# New_Multirotor_GPS.net
KiCad netlist of a schematic drawn in EAGLE
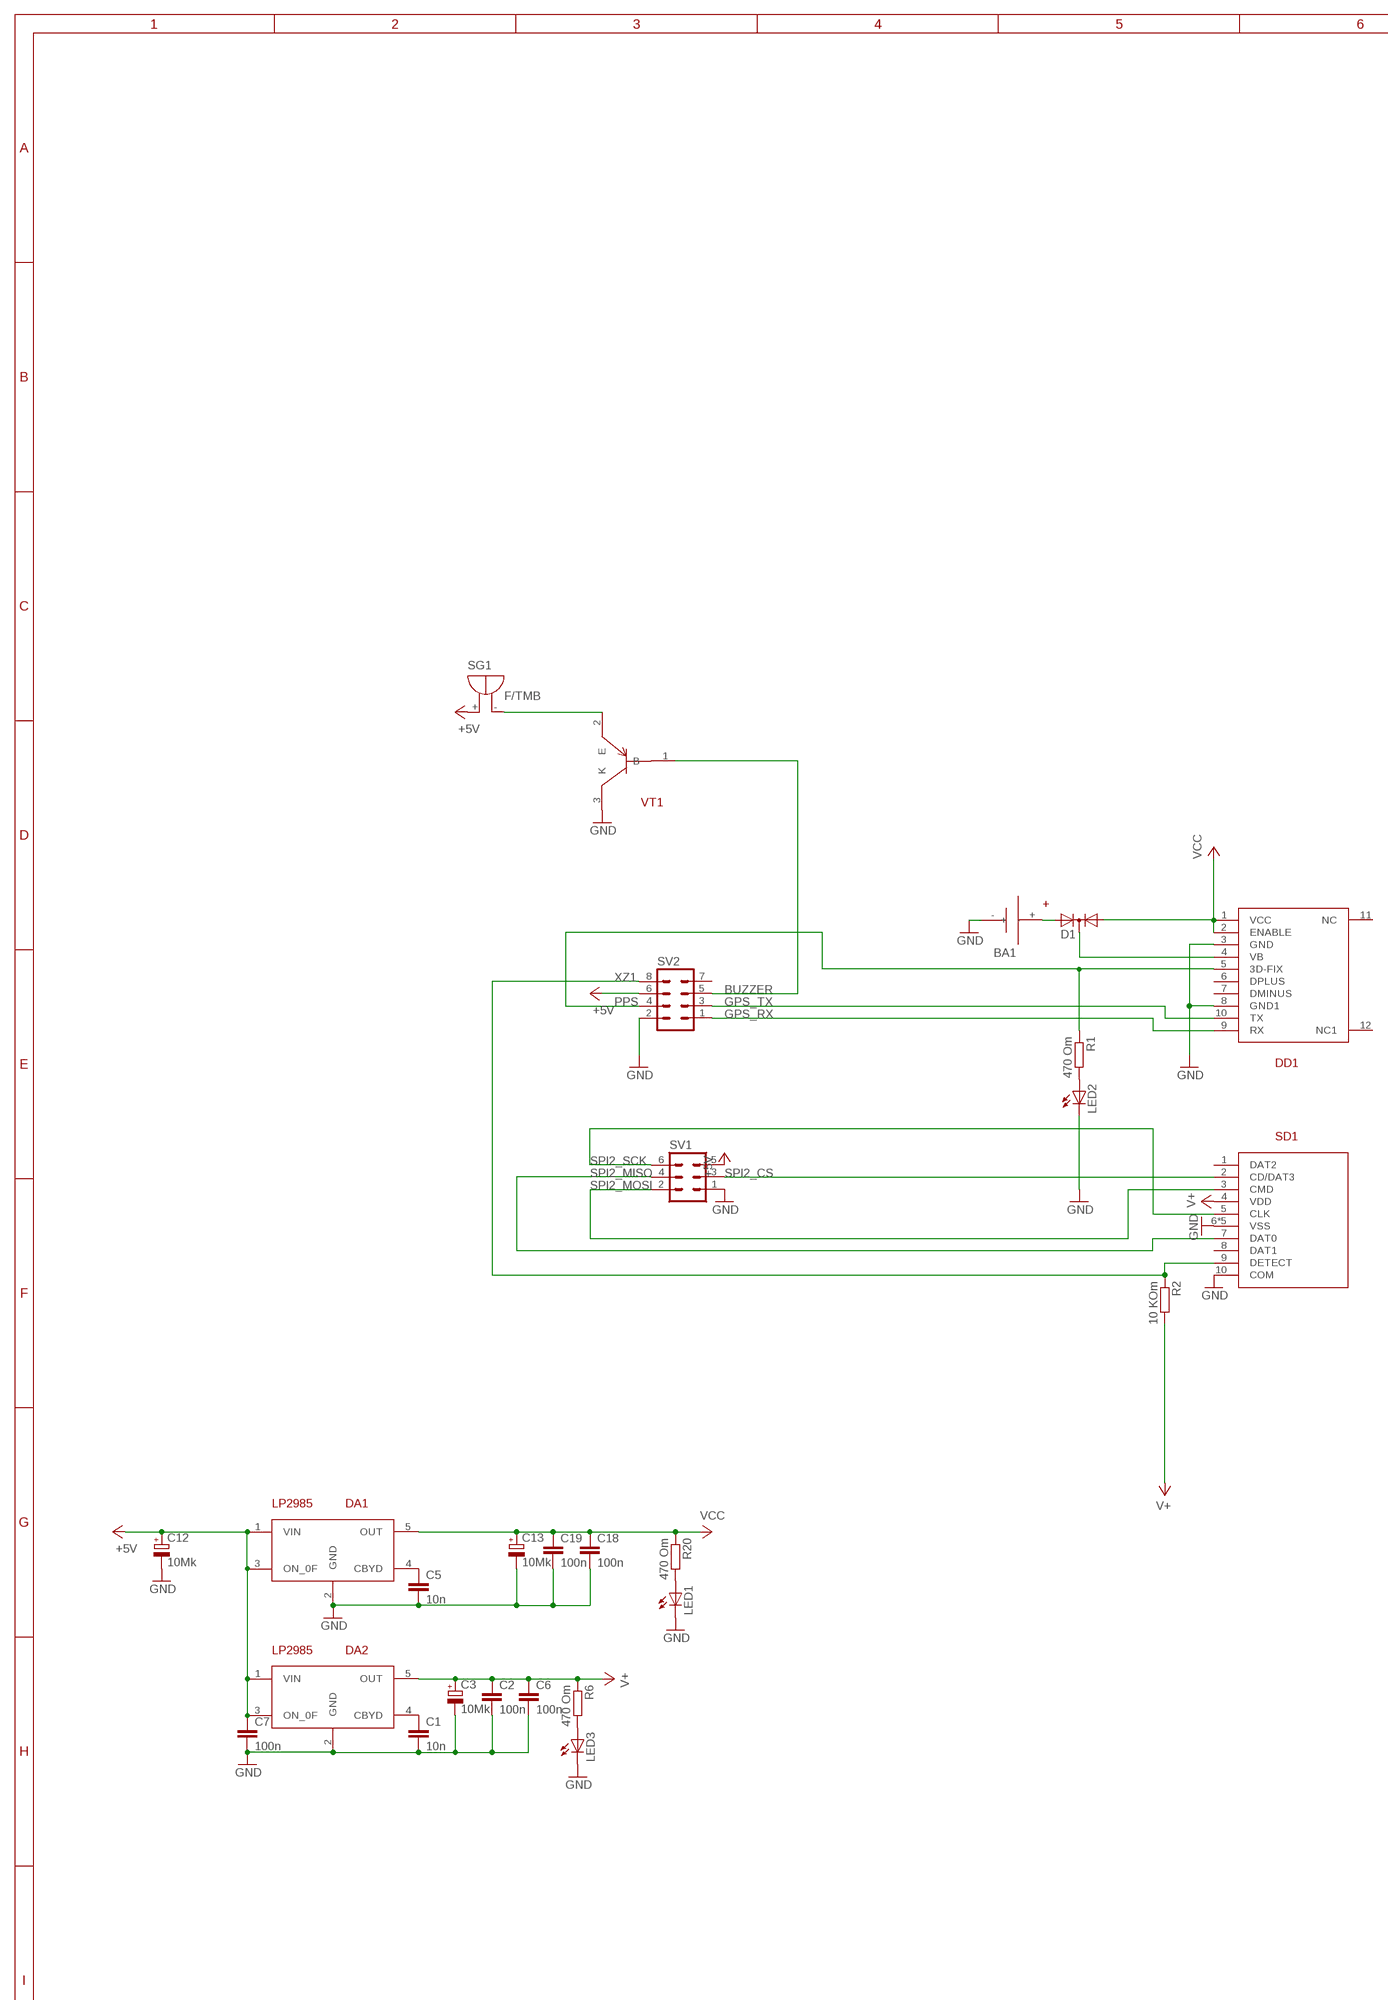
[diagram p0: schematic, sheet 1, part 1 of 2]
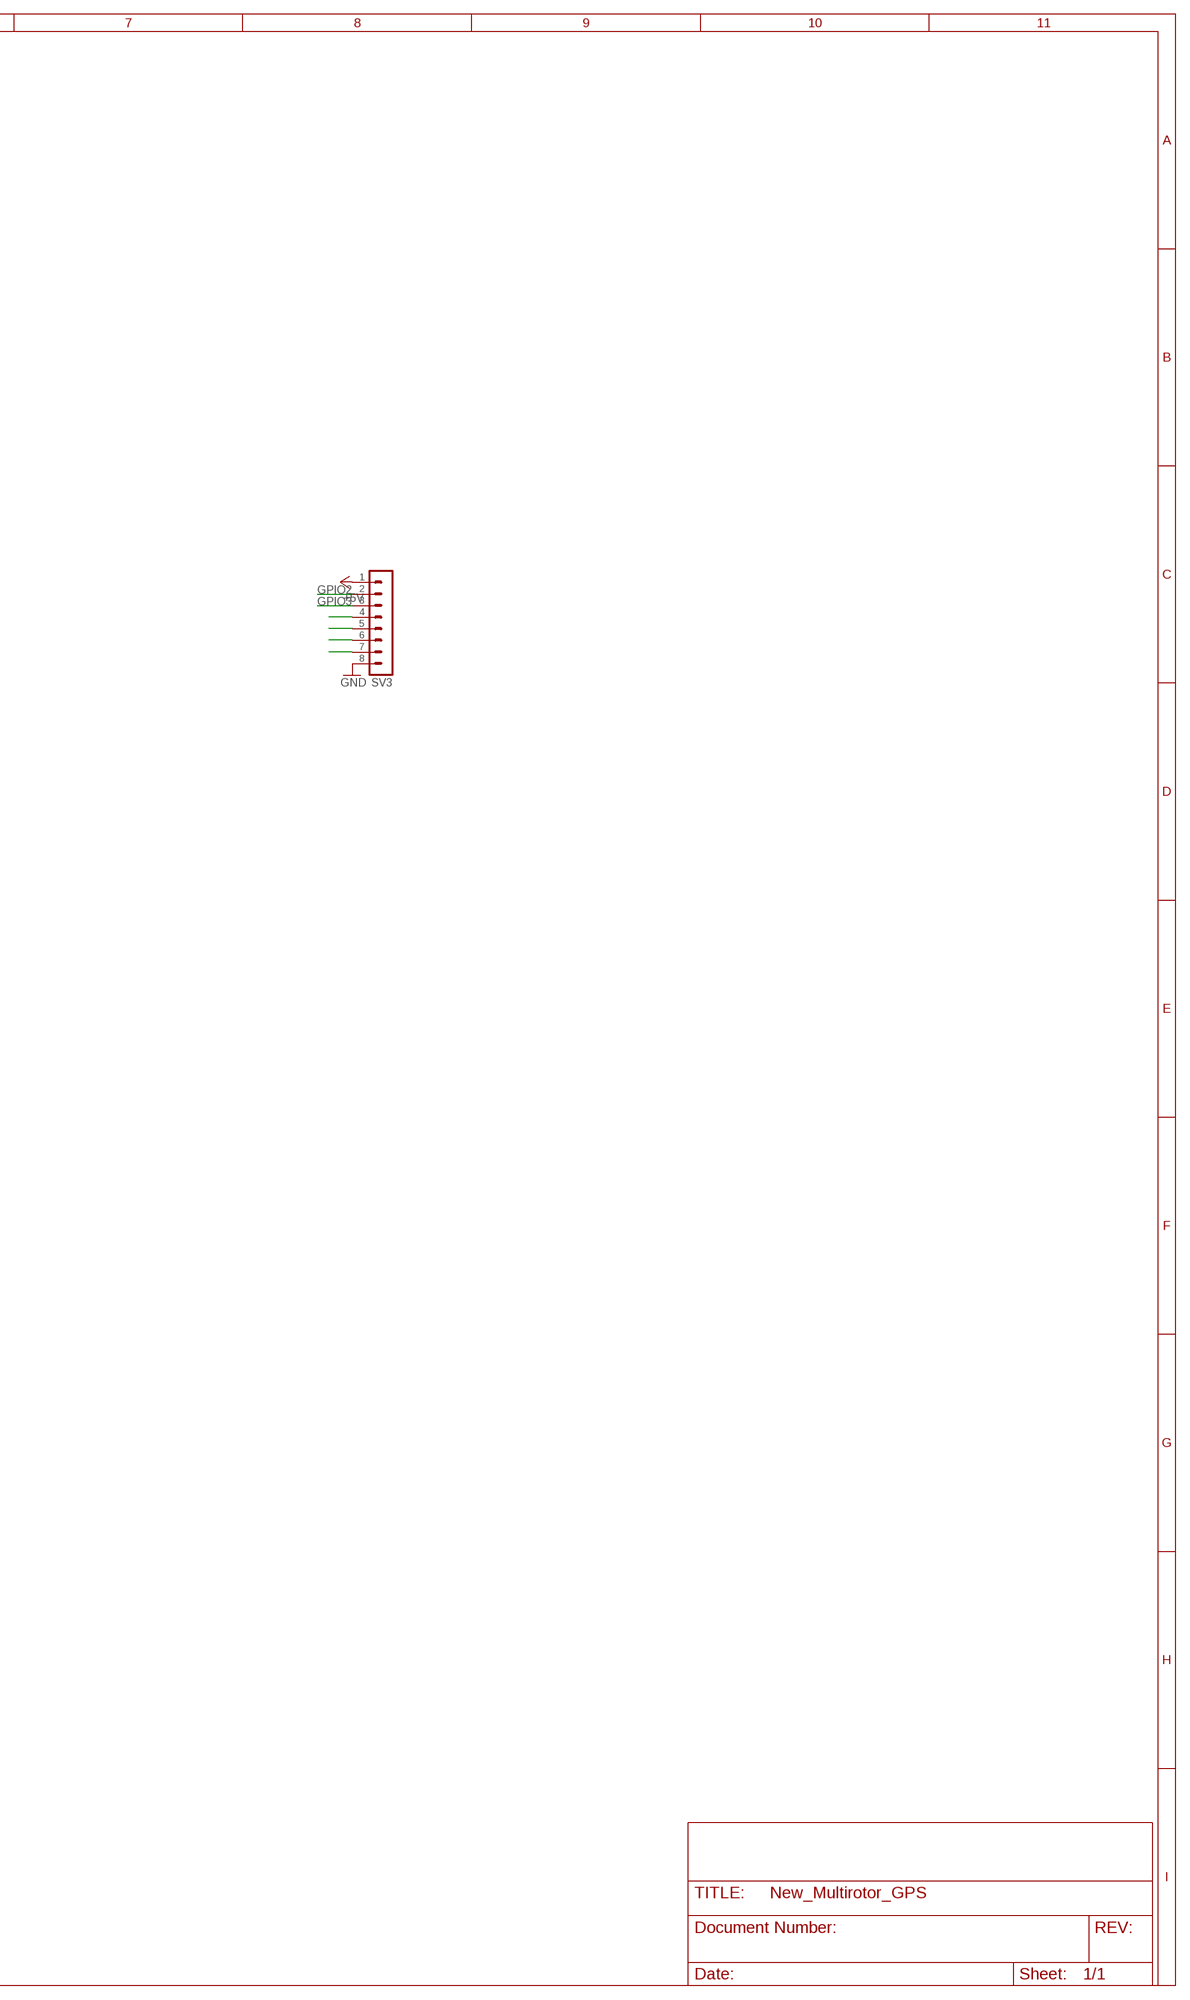
[diagram p1: schematic, sheet 1, part 2 of 2]

(export (version "E")
  (design (tool "Eeschema 10.0.6"))
  (components
    (comp (ref "BA1")
      (value "BAT")
      (footprint "eagle-import:BAT")
      (libsource (lib "eagle-import") (part "BAT"))
    )
    (comp (ref "C1")
      (value "10n")
      (footprint "eagle-import:C0603K")
      (libsource (lib "eagle-import") (part "C-EUC0603K"))
    )
    (comp (ref "C2")
      (value "100n")
      (footprint "eagle-import:C0603K")
      (libsource (lib "eagle-import") (part "C-EUC0603K"))
    )
    (comp (ref "C3")
      (value "10Mk")
      (footprint "eagle-import:A_3216-18W")
      (libsource (lib "eagle-import") (part "CPOL-EUA/3216-18W"))
    )
    (comp (ref "C5")
      (value "10n")
      (footprint "eagle-import:C0603K")
      (libsource (lib "eagle-import") (part "C-EUC0603K"))
    )
    (comp (ref "C6")
      (value "100n")
      (footprint "eagle-import:C0603K")
      (libsource (lib "eagle-import") (part "C-EUC0603K"))
    )
    (comp (ref "C7")
      (value "100n")
      (footprint "eagle-import:C0603K")
      (libsource (lib "eagle-import") (part "C-EUC0603K"))
    )
    (comp (ref "C12")
      (value "10Mk")
      (footprint "eagle-import:A_3216-18W")
      (libsource (lib "eagle-import") (part "CPOL-EUA/3216-18W"))
    )
    (comp (ref "C13")
      (value "10Mk")
      (footprint "eagle-import:A_3216-18W")
      (libsource (lib "eagle-import") (part "CPOL-EUA/3216-18W"))
    )
    (comp (ref "C18")
      (value "100n")
      (footprint "eagle-import:C0603K")
      (libsource (lib "eagle-import") (part "C-EUC0603K"))
    )
    (comp (ref "C19")
      (value "100n")
      (footprint "eagle-import:C0603K")
      (libsource (lib "eagle-import") (part "C-EUC0603K"))
    )
    (comp (ref "D1")
      (value "DIODE-2AC|CASOT23")
      (footprint "eagle-import:SOT23")
      (libsource (lib "eagle-import") (part "DIODE-2AC|CASOT23"))
    )
    (comp (ref "DA1")
      (value "LP2985")
      (footprint "eagle-import:SOT23-5L")
      (libsource (lib "eagle-import") (part "3.3"))
    )
    (comp (ref "DA2")
      (value "LP2985")
      (footprint "eagle-import:SOT23-5L")
      (libsource (lib "eagle-import") (part "3.3"))
    )
    (comp (ref "DD1")
      (value "FGPMMOPA6B")
      (footprint "eagle-import:FGPMMOPA6B")
      (libsource (lib "eagle-import") (part "FGPMMOPA6B"))
    )
    (comp (ref "LED1")
      (value "LEDCHIPLED_0603")
      (footprint "eagle-import:CHIPLED_0603")
      (libsource (lib "eagle-import") (part "LEDCHIPLED_0603"))
    )
    (comp (ref "LED2")
      (value "LEDCHIPLED_0603")
      (footprint "eagle-import:CHIPLED_0603")
      (libsource (lib "eagle-import") (part "LEDCHIPLED_0603"))
    )
    (comp (ref "LED3")
      (value "LEDCHIPLED_0603")
      (footprint "eagle-import:CHIPLED_0603")
      (libsource (lib "eagle-import") (part "LEDCHIPLED_0603"))
    )
    (comp (ref "R1")
      (value "470 Om")
      (footprint "eagle-import:R0603")
      (libsource (lib "eagle-import") (part "R-EU_R0603"))
    )
    (comp (ref "R2")
      (value "10 KOm")
      (footprint "eagle-import:R0603")
      (libsource (lib "eagle-import") (part "R-EU_R0603"))
    )
    (comp (ref "R6")
      (value "470 Om")
      (footprint "eagle-import:R0603")
      (libsource (lib "eagle-import") (part "R-EU_R0603"))
    )
    (comp (ref "R20")
      (value "470 Om")
      (footprint "eagle-import:R0603")
      (libsource (lib "eagle-import") (part "R-EU_R0603"))
    )
    (comp (ref "SD1")
      (value "MICROCD_MAIN")
      (footprint "eagle-import:MICROSD_MAIN")
      (libsource (lib "eagle-import") (part "MICROCD_MAIN"))
    )
    (comp (ref "SG1")
      (value "F/TMB")
      (footprint "eagle-import:F_TMB")
      (libsource (lib "eagle-import") (part "F/TMB"))
    )
    (comp (ref "SV1")
      (value "MA03-2")
      (footprint "eagle-import:MA03-2")
      (libsource (lib "eagle-import") (part "MA03-2"))
    )
    (comp (ref "SV2")
      (value "MA04-2")
      (footprint "eagle-import:MA04-2")
      (libsource (lib "eagle-import") (part "MA04-2"))
    )
    (comp (ref "SV3")
      (value "MA08-1")
      (footprint "eagle-import:MA08-1")
      (libsource (lib "eagle-import") (part "MA08-1"))
    )
    (comp (ref "VT1")
      (value "MMBT3906")
      (footprint "eagle-import:SOT23B-3")
      (libsource (lib "eagle-import") (part "MMBT3906"))
    )
  )
  (nets
    (net (code "1") (name "+5V") (class "Default")
      (node (ref "C12") (pin "+") (pinfunction "+_+") (pintype "passive"))
      (node (ref "C7") (pin "1") (pinfunction "1_1") (pintype "passive"))
      (node (ref "DA1") (pin "1") (pinfunction "VIN_1") (pintype "bidirectional"))
      (node (ref "DA1") (pin "3") (pinfunction "ON_0F_3") (pintype "bidirectional"))
      (node (ref "DA2") (pin "1") (pinfunction "VIN_1") (pintype "bidirectional"))
      (node (ref "DA2") (pin "3") (pinfunction "ON_0F_3") (pintype "bidirectional"))
      (node (ref "SG1") (pin "+") (pinfunction "+_+") (pintype "passive"))
      (node (ref "SV1") (pin "5") (pinfunction "5_5") (pintype "passive"))
      (node (ref "SV2") (pin "6") (pinfunction "6_6") (pintype "passive"))
      (node (ref "SV3") (pin "1") (pinfunction "1_1") (pintype "passive"))
    )
    (net (code "2") (name "/BUZZER") (class "Default")
      (node (ref "SV2") (pin "5") (pinfunction "5_5") (pintype "passive"))
      (node (ref "VT1") (pin "1") (pinfunction "B_1") (pintype "bidirectional"))
    )
    (net (code "3") (name "/GPIO2") (class "Default")
      (node (ref "SV3") (pin "2") (pinfunction "2_2") (pintype "passive"))
    )
    (net (code "4") (name "/GPIO3") (class "Default")
      (node (ref "SV3") (pin "3") (pinfunction "3_3") (pintype "passive"))
    )
    (net (code "5") (name "/GPS_RX") (class "Default")
      (node (ref "DD1") (pin "9") (pinfunction "RX_9") (pintype "bidirectional"))
      (node (ref "SV2") (pin "1") (pinfunction "1_1") (pintype "passive"))
    )
    (net (code "6") (name "/GPS_TX") (class "Default")
      (node (ref "DD1") (pin "10") (pinfunction "TX_10") (pintype "bidirectional"))
      (node (ref "SV2") (pin "3") (pinfunction "3_3") (pintype "passive"))
    )
    (net (code "7") (name "/PPS") (class "Default")
      (node (ref "DD1") (pin "5") (pinfunction "3D-FIX_5") (pintype "bidirectional"))
      (node (ref "R1") (pin "1") (pinfunction "1_1") (pintype "passive"))
      (node (ref "SV2") (pin "4") (pinfunction "4_4") (pintype "passive"))
    )
    (net (code "8") (name "/SPI2_CS") (class "Default")
      (node (ref "SD1") (pin "2") (pinfunction "CD/DAT3_2") (pintype "bidirectional"))
      (node (ref "SV1") (pin "3") (pinfunction "3_3") (pintype "passive"))
    )
    (net (code "9") (name "/SPI2_MISO") (class "Default")
      (node (ref "SD1") (pin "7") (pinfunction "DAT0_7") (pintype "bidirectional"))
      (node (ref "SV1") (pin "4") (pinfunction "4_4") (pintype "passive"))
    )
    (net (code "10") (name "/SPI2_MOSI") (class "Default")
      (node (ref "SD1") (pin "3") (pinfunction "CMD_3") (pintype "bidirectional"))
      (node (ref "SV1") (pin "2") (pinfunction "2_2") (pintype "passive"))
    )
    (net (code "11") (name "/SPI2_SCK") (class "Default")
      (node (ref "SD1") (pin "5") (pinfunction "CLK_5") (pintype "bidirectional"))
      (node (ref "SV1") (pin "6") (pinfunction "6_6") (pintype "passive"))
    )
    (net (code "12") (name "/XZ1") (class "Default")
      (node (ref "R2") (pin "1") (pinfunction "1_1") (pintype "passive"))
      (node (ref "SD1") (pin "9") (pinfunction "DETECT_9") (pintype "bidirectional"))
      (node (ref "SV2") (pin "8") (pinfunction "8_8") (pintype "passive"))
    )
    (net (code "13") (name "GND") (class "Default")
      (node (ref "BA1") (pin "-") (pinfunction "-_-") (pintype "power_in"))
      (node (ref "C1") (pin "2") (pinfunction "2_2") (pintype "passive"))
      (node (ref "C12") (pin "-") (pinfunction "-_-") (pintype "passive"))
      (node (ref "C13") (pin "-") (pinfunction "-_-") (pintype "passive"))
      (node (ref "C18") (pin "2") (pinfunction "2_2") (pintype "passive"))
      (node (ref "C19") (pin "2") (pinfunction "2_2") (pintype "passive"))
      (node (ref "C2") (pin "2") (pinfunction "2_2") (pintype "passive"))
      (node (ref "C3") (pin "-") (pinfunction "-_-") (pintype "passive"))
      (node (ref "C5") (pin "2") (pinfunction "2_2") (pintype "passive"))
      (node (ref "C6") (pin "2") (pinfunction "2_2") (pintype "passive"))
      (node (ref "C7") (pin "2") (pinfunction "2_2") (pintype "passive"))
      (node (ref "DA1") (pin "2") (pinfunction "GND_2") (pintype "bidirectional"))
      (node (ref "DA2") (pin "2") (pinfunction "GND_2") (pintype "bidirectional"))
      (node (ref "DD1") (pin "3") (pinfunction "GND_3") (pintype "bidirectional"))
      (node (ref "DD1") (pin "8") (pinfunction "GND1_8") (pintype "bidirectional"))
      (node (ref "LED1") (pin "C") (pinfunction "C_C") (pintype "passive"))
      (node (ref "LED2") (pin "C") (pinfunction "C_C") (pintype "passive"))
      (node (ref "LED3") (pin "C") (pinfunction "C_C") (pintype "passive"))
      (node (ref "SD1") (pin "10") (pinfunction "COM_10") (pintype "bidirectional"))
      (node (ref "SD1") (pin "11") (pinfunction "VSS_11") (pintype "bidirectional"))
      (node (ref "SD1") (pin "12") (pinfunction "VSS_12") (pintype "bidirectional"))
      (node (ref "SD1") (pin "13") (pinfunction "VSS_13") (pintype "bidirectional"))
      (node (ref "SD1") (pin "14") (pinfunction "VSS_14") (pintype "bidirectional"))
      (node (ref "SD1") (pin "6") (pinfunction "VSS_6") (pintype "bidirectional"))
      (node (ref "SV1") (pin "1") (pinfunction "1_1") (pintype "passive"))
      (node (ref "SV2") (pin "2") (pinfunction "2_2") (pintype "passive"))
      (node (ref "SV3") (pin "8") (pinfunction "8_8") (pintype "passive"))
      (node (ref "VT1") (pin "3") (pinfunction "K_3") (pintype "bidirectional"))
    )
    (net (code "14") (name "Net-(D1-A2)") (class "Default")
      (node (ref "BA1") (pin "+") (pinfunction "+_+") (pintype "power_in"))
      (node (ref "D1") (pin "2") (pinfunction "A2_2") (pintype "passive"))
    )
    (net (code "15") (name "Net-(D1-C)") (class "Default")
      (node (ref "D1") (pin "3") (pinfunction "C_3") (pintype "passive"))
      (node (ref "DD1") (pin "4") (pinfunction "VB_4") (pintype "bidirectional"))
    )
    (net (code "16") (name "Net-(DA1-CBYD)") (class "Default")
      (node (ref "C5") (pin "1") (pinfunction "1_1") (pintype "passive"))
      (node (ref "DA1") (pin "4") (pinfunction "CBYD_4") (pintype "bidirectional"))
    )
    (net (code "17") (name "Net-(DA2-CBYD)") (class "Default")
      (node (ref "C1") (pin "1") (pinfunction "1_1") (pintype "passive"))
      (node (ref "DA2") (pin "4") (pinfunction "CBYD_4") (pintype "bidirectional"))
    )
    (net (code "18") (name "Net-(LED1-PadA)") (class "Default")
      (node (ref "LED1") (pin "A") (pinfunction "A_A") (pintype "passive"))
      (node (ref "R20") (pin "2") (pinfunction "2_2") (pintype "passive"))
    )
    (net (code "19") (name "Net-(LED2-PadA)") (class "Default")
      (node (ref "LED2") (pin "A") (pinfunction "A_A") (pintype "passive"))
      (node (ref "R1") (pin "2") (pinfunction "2_2") (pintype "passive"))
    )
    (net (code "20") (name "Net-(LED3-PadA)") (class "Default")
      (node (ref "LED3") (pin "A") (pinfunction "A_A") (pintype "passive"))
      (node (ref "R6") (pin "2") (pinfunction "2_2") (pintype "passive"))
    )
    (net (code "21") (name "Net-(VT1-E)") (class "Default")
      (node (ref "SG1") (pin "-") (pinfunction "-_-") (pintype "passive"))
      (node (ref "VT1") (pin "2") (pinfunction "E_2") (pintype "bidirectional"))
    )
    (net (code "22") (name "V+") (class "Default")
      (node (ref "C2") (pin "1") (pinfunction "1_1") (pintype "passive"))
      (node (ref "C3") (pin "+") (pinfunction "+_+") (pintype "passive"))
      (node (ref "C6") (pin "1") (pinfunction "1_1") (pintype "passive"))
      (node (ref "DA2") (pin "5") (pinfunction "OUT_5") (pintype "bidirectional"))
      (node (ref "R2") (pin "2") (pinfunction "2_2") (pintype "passive"))
      (node (ref "R6") (pin "1") (pinfunction "1_1") (pintype "passive"))
      (node (ref "SD1") (pin "4") (pinfunction "VDD_4") (pintype "bidirectional"))
    )
    (net (code "23") (name "VCC") (class "Default")
      (node (ref "C13") (pin "+") (pinfunction "+_+") (pintype "passive"))
      (node (ref "C18") (pin "1") (pinfunction "1_1") (pintype "passive"))
      (node (ref "C19") (pin "1") (pinfunction "1_1") (pintype "passive"))
      (node (ref "D1") (pin "1") (pinfunction "A1_1") (pintype "passive"))
      (node (ref "DA1") (pin "5") (pinfunction "OUT_5") (pintype "bidirectional"))
      (node (ref "DD1") (pin "1") (pinfunction "VCC_1") (pintype "bidirectional"))
      (node (ref "DD1") (pin "2") (pinfunction "ENABLE_2") (pintype "bidirectional"))
      (node (ref "R20") (pin "1") (pinfunction "1_1") (pintype "passive"))
    )
    (net (code "24") (name "unconnected-(DD1-DMINUS-Pad7)") (class "Default")
      (node (ref "DD1") (pin "7") (pinfunction "DMINUS_7") (pintype "bidirectional"))
    )
    (net (code "25") (name "unconnected-(DD1-DPLUS-Pad6)") (class "Default")
      (node (ref "DD1") (pin "6") (pinfunction "DPLUS_6") (pintype "bidirectional"))
    )
    (net (code "26") (name "unconnected-(DD1-NC-Pad11)") (class "Default")
      (node (ref "DD1") (pin "11") (pinfunction "NC_11") (pintype "bidirectional"))
    )
    (net (code "27") (name "unconnected-(DD1-NC1-Pad12)") (class "Default")
      (node (ref "DD1") (pin "12") (pinfunction "NC1_12") (pintype "bidirectional"))
    )
    (net (code "28") (name "unconnected-(SD1-DAT1-Pad8)") (class "Default")
      (node (ref "SD1") (pin "8") (pinfunction "DAT1_8") (pintype "bidirectional"))
    )
    (net (code "29") (name "unconnected-(SD1-DAT2-Pad1)") (class "Default")
      (node (ref "SD1") (pin "1") (pinfunction "DAT2_1") (pintype "bidirectional"))
    )
    (net (code "30") (name "unconnected-(SV2-Pad7)") (class "Default")
      (node (ref "SV2") (pin "7") (pinfunction "7_7") (pintype "passive"))
    )
    (net (code "31") (name "unconnected-(SV3-Pad4)") (class "Default")
      (node (ref "SV3") (pin "4") (pinfunction "4_4") (pintype "passive"))
    )
    (net (code "32") (name "unconnected-(SV3-Pad5)") (class "Default")
      (node (ref "SV3") (pin "5") (pinfunction "5_5") (pintype "passive"))
    )
    (net (code "33") (name "unconnected-(SV3-Pad6)") (class "Default")
      (node (ref "SV3") (pin "6") (pinfunction "6_6") (pintype "passive"))
    )
    (net (code "34") (name "unconnected-(SV3-Pad7)") (class "Default")
      (node (ref "SV3") (pin "7") (pinfunction "7_7") (pintype "passive"))
    )
  )
)
